# SCH_Better_Contoller_2022-11-13.net
KiCad netlist of a schematic drawn in EasyEDA
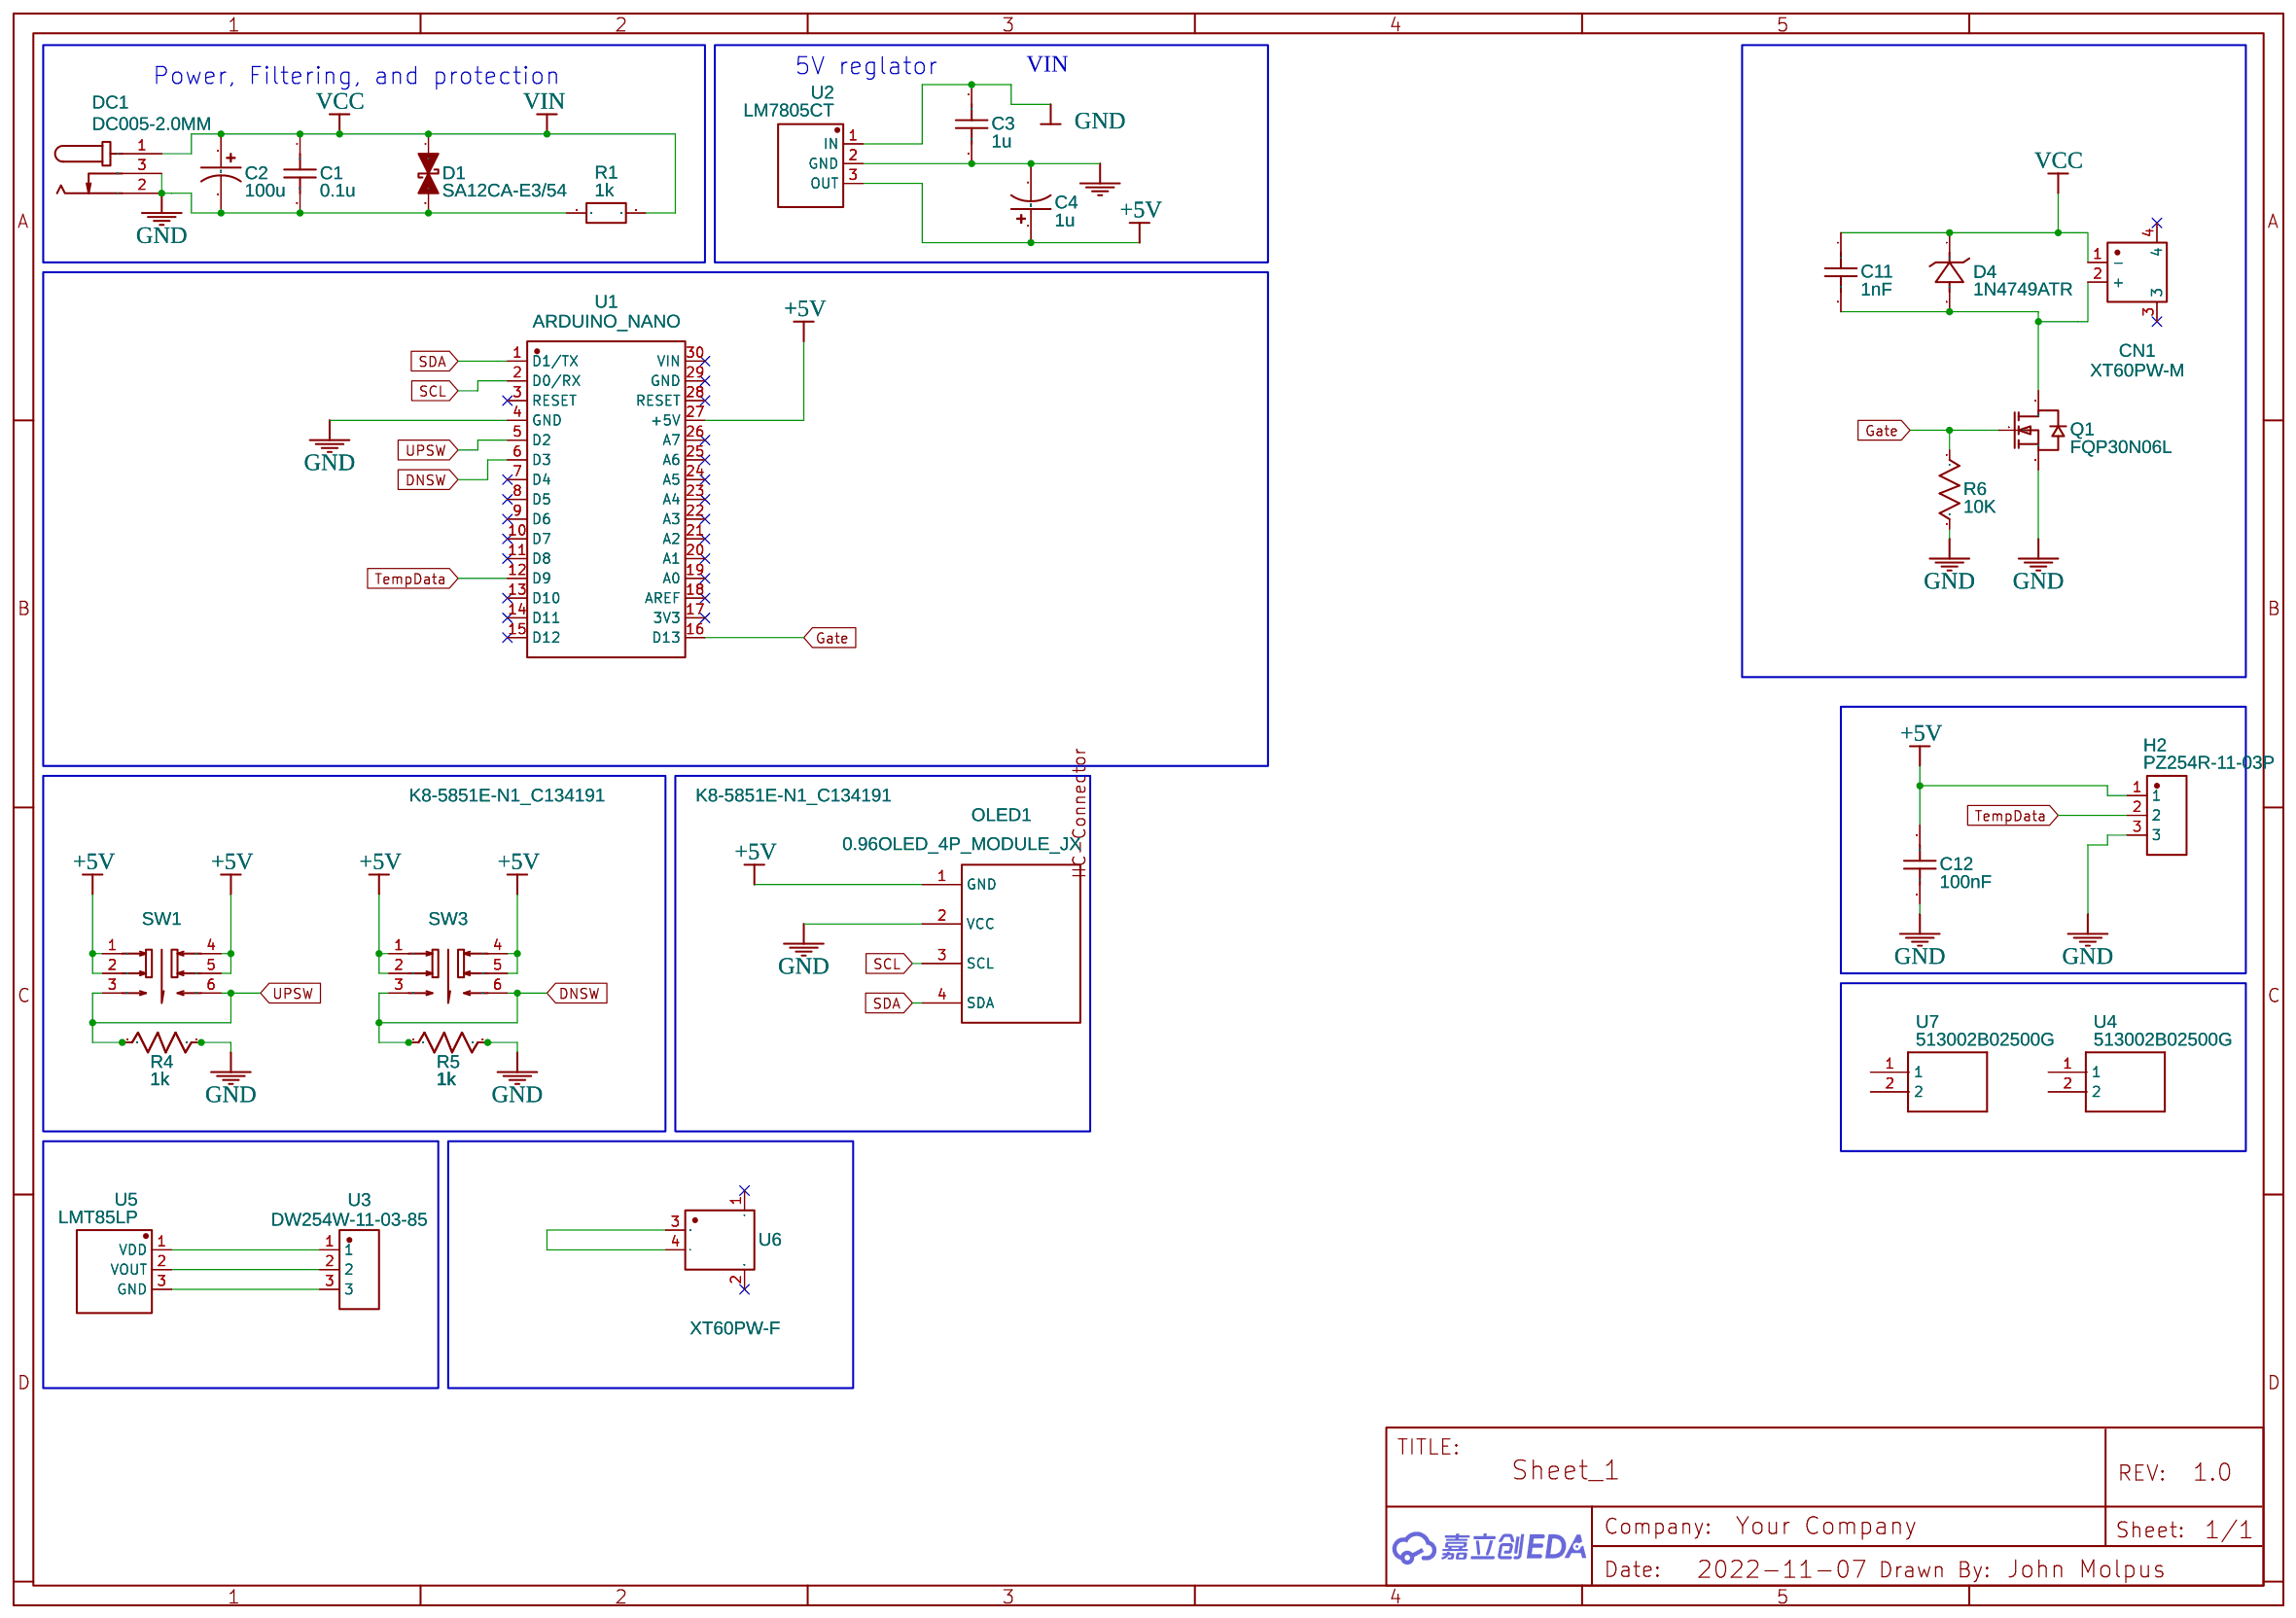
[diagram p0: schematic sheet]

(export (version "E")
  (design (tool "Eeschema 10.0.6"))
  (components
    (comp (ref "C1") (value "0.1u") (libsource (lib "") (part "C_RAD-0.2_US")))
    (comp (ref "C2") (value "100u") (libsource (lib "") (part "CE_TH_D3.0×F1.5_US")))
    (comp (ref "C3") (value "1u") (libsource (lib "") (part "C_RAD-0.1_US")))
    (comp (ref "C4") (value "1u") (libsource (lib "") (part "CE_TH_D3.0×F1.5_US_1")))
    (comp (ref "C11") (value "1nF") (libsource (lib "") (part "C_RAD-0.1_US")))
    (comp (ref "C12") (value "100nF") (libsource (lib "") (part "C_RAD-0.1_US")))
    (comp (ref "CN1")
      (value "XT60PW-M")
      (fields (field (name "BOM_Supplier Part") "C98732"))
      (libsource (lib "") (part "XT60PW-M"))
    )
    (comp (ref "D1")
      (value "SA12CA-E3/54")
      (fields (field (name "BOM_Supplier Part") "C1975517"))
      (libsource (lib "") (part "SA12CA-E3/54"))
    )
    (comp (ref "D4")
      (value "1N4749ATR")
      (fields (field (name "BOM_Supplier Part") "C890088"))
      (libsource (lib "") (part "1N4749ATR"))
    )
    (comp (ref "DC1")
      (value "DC005-2.0MM")
      (fields (field (name "BOM_Supplier Part") "C111567"))
      (libsource (lib "") (part "DC005-2.0MM"))
    )
    (comp (ref "H2")
      (value "PZ254R-11-03P")
      (fields (field (name "BOM_Supplier Part") "C492411"))
      (libsource (lib "") (part "PZ254R-11-03P"))
    )
    (comp (ref "OLED1")
      (value "0.96OLED_4P_MODULE_JX")
      (fields (field (name "BOM_Supplier Part") "C9900004566"))
      (libsource (lib "") (part "0.96OLED_4P_MODULE_JX"))
    )
    (comp (ref "Q1")
      (value "FQP30N06L")
      (fields
        (field (name "BOM_Manufacturer Part") "FQP30N06L-VB")
        (field (name "BOM_Supplier Part") "C878826")
      )
      (libsource (lib "") (part "FQP30N06L"))
    )
    (comp (ref "R1") (value "1k") (libsource (lib "") (part "R_AXIAL-0.3_EU")))
    (comp (ref "R2") (value "1k") (libsource (lib "") (part "R_AXIAL-0.3_US")))
    (comp (ref "R4") (value "1k") (libsource (lib "") (part "R_AXIAL-0.3_US")))
    (comp (ref "R5") (value "1k") (libsource (lib "") (part "R_AXIAL-0.3_US")))
    (comp (ref "R6") (value "10K") (libsource (lib "") (part "R_AXIAL-0.3_US_1")))
    (comp (ref "R7") (value "1k") (libsource (lib "") (part "R_AXIAL-0.3_US")))
    (comp (ref "SW1")
      (value "K8-5851E-N1_C134191")
      (fields
        (field (name "BOM_Manufacturer Part") "K8-5851E-N1")
        (field (name "BOM_Supplier Part") "C134191")
      )
      (libsource (lib "") (part "K8-5851E-N1_C134191"))
    )
    (comp (ref "SW3")
      (value "K8-5851E-N1_C134191")
      (fields
        (field (name "BOM_Manufacturer Part") "K8-5851E-N1")
        (field (name "BOM_Supplier Part") "C134191")
      )
      (libsource (lib "") (part "K8-5851E-N1_C134191"))
    )
    (comp (ref "U1")
      (value "ARDUINO_NANO")
      (fields (field (name "BOM_Supplier Part") "C9900017879"))
      (libsource (lib "") (part "ARDUINO_NANO"))
    )
    (comp (ref "U2")
      (value "LM7805CT")
      (fields (field (name "BOM_Supplier Part") "C22146"))
      (libsource (lib "") (part "LM7805CT"))
    )
    (comp (ref "U3")
      (value "DW254W-11-03-85")
      (fields (field (name "BOM_Supplier Part") "C2935993"))
      (libsource (lib "") (part "DW254W-11-03-85"))
    )
    (comp (ref "U4") (value "513002B02500G") (libsource (lib "") (part "513002B02500G")))
    (comp (ref "U5")
      (value "LMT85LP")
      (fields (field (name "BOM_Supplier Part") "C75856"))
      (libsource (lib "") (part "LMT85LP"))
    )
    (comp (ref "U6")
      (value "XT60PW-F")
      (fields
        (field (name "BOM_Manufacturer Part") "XT60PW-F 母头 板插卧式")
        (field (name "BOM_Supplier Part") "C9900000737")
      )
      (libsource (lib "") (part "XT60PW-F"))
    )
    (comp (ref "U7") (value "513002B02500G") (libsource (lib "") (part "513002B02500G")))
  )
  (nets
    (net (code "1") (name "+5V") (class "Default")
      (node (ref "C12") (pin "1") (pinfunction "1_1") (pintype "unspecified"))
      (node (ref "C4") (pin "1") (pinfunction "1_1") (pintype "unspecified"))
      (node (ref "H2") (pin "1") (pinfunction "1_1") (pintype "unspecified"))
      (node (ref "OLED1") (pin "1") (pinfunction "GND_1") (pintype "unspecified"))
      (node (ref "SW1") (pin "1") (pinfunction "1_1") (pintype "unspecified"))
      (node (ref "SW1") (pin "2") (pinfunction "2_2") (pintype "unspecified"))
      (node (ref "SW1") (pin "4") (pinfunction "4_4") (pintype "unspecified"))
      (node (ref "SW1") (pin "5") (pinfunction "5_5") (pintype "unspecified"))
      (node (ref "SW3") (pin "1") (pinfunction "1_1") (pintype "unspecified"))
      (node (ref "SW3") (pin "2") (pinfunction "2_2") (pintype "unspecified"))
      (node (ref "SW3") (pin "4") (pinfunction "4_4") (pintype "unspecified"))
      (node (ref "SW3") (pin "5") (pinfunction "5_5") (pintype "unspecified"))
      (node (ref "U1") (pin "27") (pinfunction "+5V_27") (pintype "unspecified"))
      (node (ref "U2") (pin "3") (pinfunction "OUT_3") (pintype "unspecified"))
    )
    (net (code "2") (name "DNSW") (class "Default")
      (node (ref "R5") (pin "1") (pinfunction "1_1") (pintype "unspecified"))
      (node (ref "R7") (pin "1") (pinfunction "1_1") (pintype "unspecified"))
      (node (ref "SW3") (pin "3") (pinfunction "3_3") (pintype "unspecified"))
      (node (ref "SW3") (pin "6") (pinfunction "6_6") (pintype "unspecified"))
      (node (ref "U1") (pin "6") (pinfunction "D3_6") (pintype "unspecified"))
    )
    (net (code "3") (name "GND") (class "Default")
      (node (ref "C1") (pin "2") (pinfunction "2_2") (pintype "unspecified"))
      (node (ref "C12") (pin "2") (pinfunction "2_2") (pintype "unspecified"))
      (node (ref "C2") (pin "2") (pinfunction "2_2") (pintype "unspecified"))
      (node (ref "C3") (pin "2") (pinfunction "2_2") (pintype "unspecified"))
      (node (ref "C4") (pin "2") (pinfunction "2_2") (pintype "unspecified"))
      (node (ref "D1") (pin "2") (pinfunction "A_2") (pintype "input"))
      (node (ref "DC1") (pin "2") (pinfunction "2_2") (pintype "unspecified"))
      (node (ref "DC1") (pin "3") (pinfunction "3_3") (pintype "unspecified"))
      (node (ref "H2") (pin "3") (pinfunction "3_3") (pintype "unspecified"))
      (node (ref "OLED1") (pin "2") (pinfunction "VCC_2") (pintype "unspecified"))
      (node (ref "Q1") (pin "3") (pinfunction "S_3") (pintype "unspecified"))
      (node (ref "R1") (pin "1") (pinfunction "1_1") (pintype "unspecified"))
      (node (ref "R2") (pin "2") (pinfunction "2_2") (pintype "unspecified"))
      (node (ref "R4") (pin "2") (pinfunction "2_2") (pintype "unspecified"))
      (node (ref "R5") (pin "2") (pinfunction "2_2") (pintype "unspecified"))
      (node (ref "R6") (pin "2") (pinfunction "2_2") (pintype "unspecified"))
      (node (ref "R7") (pin "2") (pinfunction "2_2") (pintype "unspecified"))
      (node (ref "U1") (pin "4") (pinfunction "GND_4") (pintype "unspecified"))
      (node (ref "U2") (pin "2") (pinfunction "GND_2") (pintype "unspecified"))
    )
    (net (code "4") (name "Gate") (class "Default")
      (node (ref "Q1") (pin "1") (pinfunction "G_1") (pintype "unspecified"))
      (node (ref "R6") (pin "1") (pinfunction "1_1") (pintype "unspecified"))
      (node (ref "U1") (pin "16") (pinfunction "D13_16") (pintype "unspecified"))
    )
    (net (code "5") (name "Net-(CN1-+)") (class "Default")
      (node (ref "C11") (pin "2") (pinfunction "2_2") (pintype "unspecified"))
      (node (ref "CN1") (pin "2") (pinfunction "+_2") (pintype "unspecified"))
      (node (ref "D4") (pin "2") (pinfunction "A_2") (pintype "unspecified"))
      (node (ref "Q1") (pin "2") (pinfunction "D_2") (pintype "unspecified"))
    )
    (net (code "6") (name "Net-(U5-GND)") (class "Default")
      (node (ref "U3") (pin "3") (pinfunction "3_3") (pintype "unspecified"))
      (node (ref "U5") (pin "3") (pinfunction "GND_3") (pintype "unspecified"))
    )
    (net (code "7") (name "Net-(U5-VDD)") (class "Default")
      (node (ref "U3") (pin "1") (pinfunction "1_1") (pintype "unspecified"))
      (node (ref "U5") (pin "1") (pinfunction "VDD_1") (pintype "unspecified"))
    )
    (net (code "8") (name "Net-(U5-VOUT)") (class "Default")
      (node (ref "U3") (pin "2") (pinfunction "2_2") (pintype "unspecified"))
      (node (ref "U5") (pin "2") (pinfunction "VOUT_2") (pintype "unspecified"))
    )
    (net (code "9") (name "Net-(U6-Pad3)") (class "Default")
      (node (ref "U6") (pin "3") (pinfunction "3_3") (pintype "unspecified"))
      (node (ref "U6") (pin "4") (pinfunction "4_4") (pintype "unspecified"))
    )
    (net (code "10") (name "SCL") (class "Default")
      (node (ref "OLED1") (pin "3") (pinfunction "SCL_3") (pintype "unspecified"))
      (node (ref "U1") (pin "2") (pinfunction "D0/RX_2") (pintype "unspecified"))
    )
    (net (code "11") (name "SDA") (class "Default")
      (node (ref "OLED1") (pin "4") (pinfunction "SDA_4") (pintype "unspecified"))
      (node (ref "U1") (pin "1") (pinfunction "D1/TX_1") (pintype "unspecified"))
    )
    (net (code "12") (name "TempData") (class "Default")
      (node (ref "H2") (pin "2") (pinfunction "2_2") (pintype "unspecified"))
      (node (ref "U1") (pin "12") (pinfunction "D9_12") (pintype "unspecified"))
    )
    (net (code "13") (name "UPSW") (class "Default")
      (node (ref "R2") (pin "1") (pinfunction "1_1") (pintype "unspecified"))
      (node (ref "R4") (pin "1") (pinfunction "1_1") (pintype "unspecified"))
      (node (ref "SW1") (pin "3") (pinfunction "3_3") (pintype "unspecified"))
      (node (ref "SW1") (pin "6") (pinfunction "6_6") (pintype "unspecified"))
      (node (ref "U1") (pin "5") (pinfunction "D2_5") (pintype "unspecified"))
    )
    (net (code "14") (name "VCC") (class "Default")
      (node (ref "C1") (pin "1") (pinfunction "1_1") (pintype "unspecified"))
      (node (ref "C11") (pin "1") (pinfunction "1_1") (pintype "unspecified"))
      (node (ref "C2") (pin "1") (pinfunction "1_1") (pintype "unspecified"))
      (node (ref "C3") (pin "1") (pinfunction "1_1") (pintype "unspecified"))
      (node (ref "CN1") (pin "1") (pinfunction "-_1") (pintype "unspecified"))
      (node (ref "D1") (pin "1") (pinfunction "K_1") (pintype "input"))
      (node (ref "D4") (pin "1") (pinfunction "C_1") (pintype "unspecified"))
      (node (ref "DC1") (pin "1") (pinfunction "1_1") (pintype "unspecified"))
      (node (ref "R1") (pin "2") (pinfunction "2_2") (pintype "unspecified"))
      (node (ref "U2") (pin "1") (pinfunction "IN_1") (pintype "unspecified"))
    )
    (net (code "15") (name "unconnected-(CN1-Pad3)") (class "Default")
      (node (ref "CN1") (pin "3") (pinfunction "3_3") (pintype "unspecified+no_connect"))
    )
    (net (code "16") (name "unconnected-(CN1-Pad4)") (class "Default")
      (node (ref "CN1") (pin "4") (pinfunction "4_4") (pintype "unspecified+no_connect"))
    )
    (net (code "17") (name "unconnected-(U1-3V3-Pad17)") (class "Default")
      (node (ref "U1") (pin "17") (pinfunction "3V3_17") (pintype "unspecified+no_connect"))
    )
    (net (code "18") (name "unconnected-(U1-A0-Pad19)") (class "Default")
      (node (ref "U1") (pin "19") (pinfunction "A0_19") (pintype "unspecified+no_connect"))
    )
    (net (code "19") (name "unconnected-(U1-A1-Pad20)") (class "Default")
      (node (ref "U1") (pin "20") (pinfunction "A1_20") (pintype "unspecified+no_connect"))
    )
    (net (code "20") (name "unconnected-(U1-A2-Pad21)") (class "Default")
      (node (ref "U1") (pin "21") (pinfunction "A2_21") (pintype "unspecified+no_connect"))
    )
    (net (code "21") (name "unconnected-(U1-A3-Pad22)") (class "Default")
      (node (ref "U1") (pin "22") (pinfunction "A3_22") (pintype "unspecified+no_connect"))
    )
    (net (code "22") (name "unconnected-(U1-A4-Pad23)") (class "Default")
      (node (ref "U1") (pin "23") (pinfunction "A4_23") (pintype "unspecified+no_connect"))
    )
    (net (code "23") (name "unconnected-(U1-A5-Pad24)") (class "Default")
      (node (ref "U1") (pin "24") (pinfunction "A5_24") (pintype "unspecified+no_connect"))
    )
    (net (code "24") (name "unconnected-(U1-A6-Pad25)") (class "Default")
      (node (ref "U1") (pin "25") (pinfunction "A6_25") (pintype "unspecified+no_connect"))
    )
    (net (code "25") (name "unconnected-(U1-A7-Pad26)") (class "Default")
      (node (ref "U1") (pin "26") (pinfunction "A7_26") (pintype "unspecified+no_connect"))
    )
    (net (code "26") (name "unconnected-(U1-AREF-Pad18)") (class "Default")
      (node (ref "U1") (pin "18") (pinfunction "AREF_18") (pintype "unspecified+no_connect"))
    )
    (net (code "27") (name "unconnected-(U1-D4-Pad7)") (class "Default")
      (node (ref "U1") (pin "7") (pinfunction "D4_7") (pintype "unspecified+no_connect"))
    )
    (net (code "28") (name "unconnected-(U1-D5-Pad8)") (class "Default")
      (node (ref "U1") (pin "8") (pinfunction "D5_8") (pintype "unspecified+no_connect"))
    )
    (net (code "29") (name "unconnected-(U1-D6-Pad9)") (class "Default")
      (node (ref "U1") (pin "9") (pinfunction "D6_9") (pintype "unspecified+no_connect"))
    )
    (net (code "30") (name "unconnected-(U1-D7-Pad10)") (class "Default")
      (node (ref "U1") (pin "10") (pinfunction "D7_10") (pintype "unspecified+no_connect"))
    )
    (net (code "31") (name "unconnected-(U1-D8-Pad11)") (class "Default")
      (node (ref "U1") (pin "11") (pinfunction "D8_11") (pintype "unspecified+no_connect"))
    )
    (net (code "32") (name "unconnected-(U1-D10-Pad13)") (class "Default")
      (node (ref "U1") (pin "13") (pinfunction "D10_13") (pintype "unspecified+no_connect"))
    )
    (net (code "33") (name "unconnected-(U1-D11-Pad14)") (class "Default")
      (node (ref "U1") (pin "14") (pinfunction "D11_14") (pintype "unspecified+no_connect"))
    )
    (net (code "34") (name "unconnected-(U1-D12-Pad15)") (class "Default")
      (node (ref "U1") (pin "15") (pinfunction "D12_15") (pintype "unspecified+no_connect"))
    )
    (net (code "35") (name "unconnected-(U1-GND-Pad29)") (class "Default")
      (node (ref "U1") (pin "29") (pinfunction "GND_29") (pintype "unspecified+no_connect"))
    )
    (net (code "36") (name "unconnected-(U1-RESET-Pad3)") (class "Default")
      (node (ref "U1") (pin "3") (pinfunction "RESET_3") (pintype "unspecified+no_connect"))
    )
    (net (code "37") (name "unconnected-(U1-RESET-Pad28)") (class "Default")
      (node (ref "U1") (pin "28") (pinfunction "RESET_28") (pintype "unspecified+no_connect"))
    )
    (net (code "38") (name "unconnected-(U1-VIN-Pad30)") (class "Default")
      (node (ref "U1") (pin "30") (pinfunction "VIN_30") (pintype "unspecified+no_connect"))
    )
    (net (code "39") (name "unconnected-(U4-Pad1)") (class "Default")
      (node (ref "U4") (pin "1") (pinfunction "1_1") (pintype "bidirectional"))
    )
    (net (code "40") (name "unconnected-(U4-Pad2)") (class "Default")
      (node (ref "U4") (pin "2") (pinfunction "2_2") (pintype "bidirectional"))
    )
    (net (code "41") (name "unconnected-(U6-Pad1)") (class "Default")
      (node (ref "U6") (pin "1") (pinfunction "1_1") (pintype "unspecified+no_connect"))
    )
    (net (code "42") (name "unconnected-(U6-Pad2)") (class "Default")
      (node (ref "U6") (pin "2") (pinfunction "2_2") (pintype "unspecified+no_connect"))
    )
    (net (code "43") (name "unconnected-(U7-Pad1)") (class "Default")
      (node (ref "U7") (pin "1") (pinfunction "1_1") (pintype "bidirectional"))
    )
    (net (code "44") (name "unconnected-(U7-Pad2)") (class "Default")
      (node (ref "U7") (pin "2") (pinfunction "2_2") (pintype "bidirectional"))
    )
  )
)
